# Sheet1_4651_MEZ.net
KiCad netlist of a schematic drawn in Altium Designer
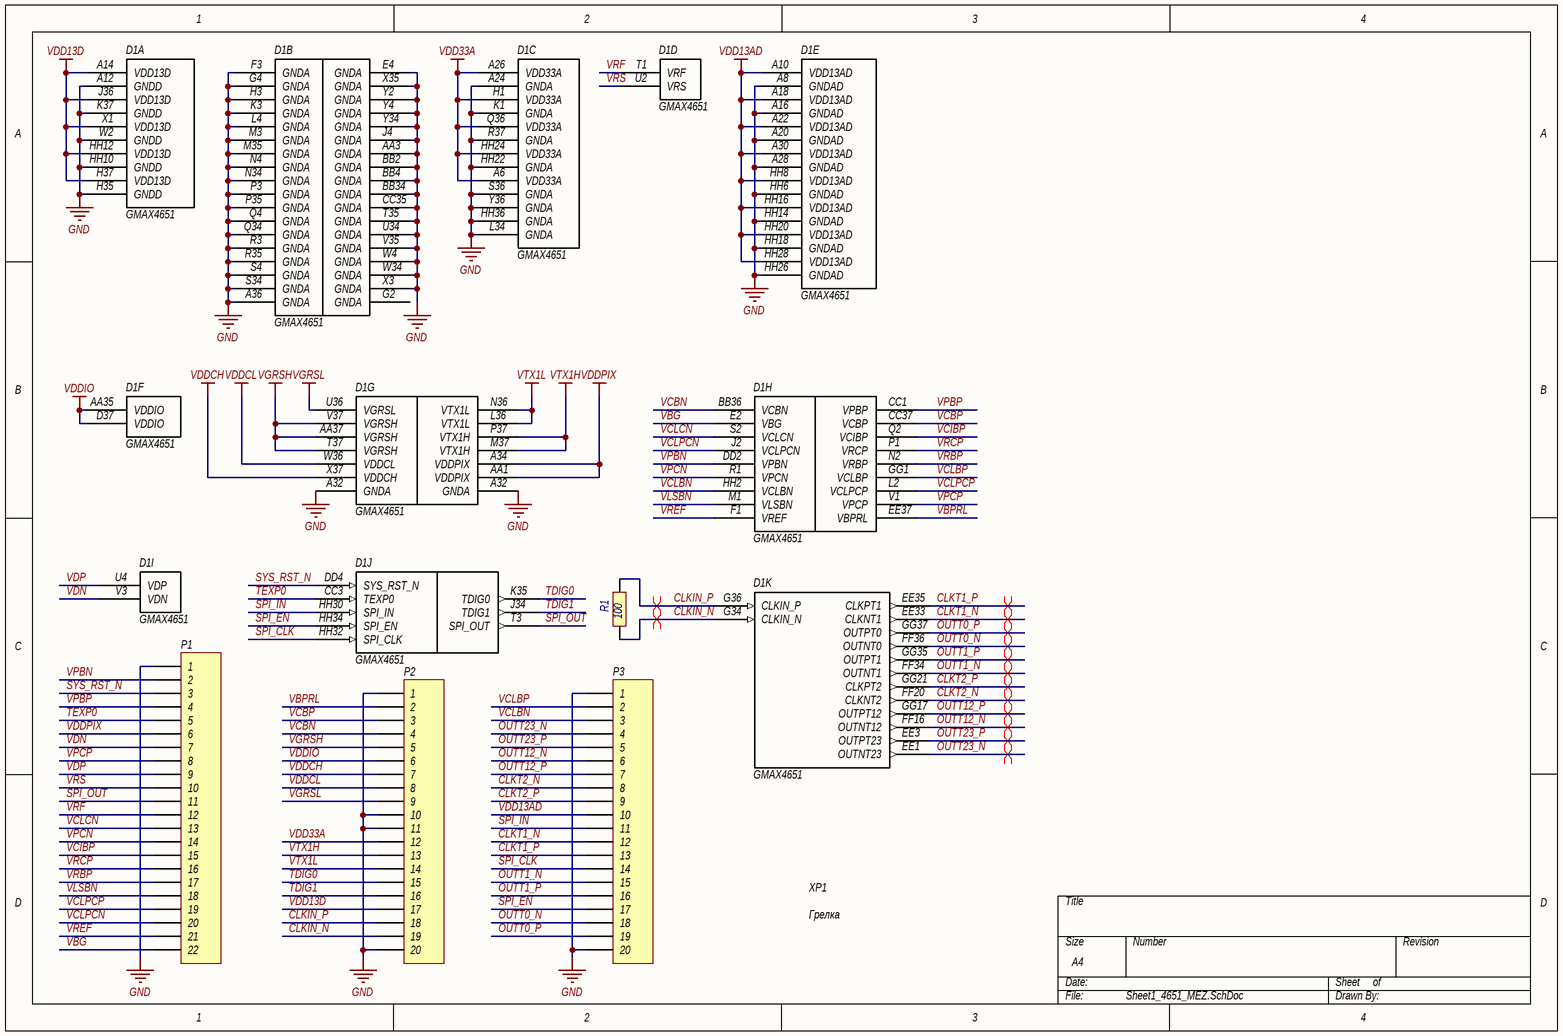
[diagram p0: Sheet1_4651_MEZ.SchDoc]

(export (version "E")
  (design (tool "Eeschema 10.0.6"))
  (components
    (comp (ref "D1") (value "GMAX4651") (footprint "GMAX4651") (libsource (lib "Schlib") (part "GMAX4651")))
    (comp (ref "P1")
      (value "Header 22")
      (footprint "HDR1X22")
      (description "Header, 22-Pin")
      (fields (field (name "PUBLISHER") "Altium Limited"))
      (libsource (lib "Miscellaneous Connectors") (part "Header 22"))
    )
    (comp (ref "P2")
      (value "Header 20")
      (footprint "HDR1X20")
      (description "Header, 20-Pin")
      (fields (field (name "PUBLISHER") "Altium Limited"))
      (libsource (lib "Miscellaneous Connectors") (part "Header 20"))
    )
    (comp (ref "P3")
      (value "Header 20")
      (footprint "HDR1X20")
      (description "Header, 20-Pin")
      (fields (field (name "PUBLISHER") "Altium Limited"))
      (libsource (lib "Miscellaneous Connectors") (part "Header 20"))
    )
    (comp (ref "R1") (value "100") (footprint "RES") (libsource (lib "Schlib") (part "RES")))
    (comp (ref "XP1") (value "Грелка") (footprint "Грелка") (libsource (lib "VPL") (part "Грелка")))
  )
  (nets
    (net (code "1") (name "/CLKIN_N") (class "Default")
      (node (ref "D1") (pin "G34") (pinfunction "CLKIN_N_G34") (pintype "input"))
      (node (ref "P2") (pin "19") (pinfunction "19_19") (pintype "passive"))
      (node (ref "R1") (pin "1") (pinfunction "1_1") (pintype "passive"))
    )
    (net (code "2") (name "/CLKIN_P") (class "Default")
      (node (ref "D1") (pin "G36") (pinfunction "CLKIN_P_G36") (pintype "input"))
      (node (ref "P2") (pin "18") (pinfunction "18_18") (pintype "passive"))
      (node (ref "R1") (pin "2") (pinfunction "2_2") (pintype "passive"))
    )
    (net (code "3") (name "/CLKT1_N") (class "Default")
      (node (ref "D1") (pin "EE33") (pinfunction "CLKNT1_EE33") (pintype "output"))
      (node (ref "P3") (pin "12") (pinfunction "12_12") (pintype "passive"))
    )
    (net (code "4") (name "/CLKT1_P") (class "Default")
      (node (ref "D1") (pin "EE35") (pinfunction "CLKPT1_EE35") (pintype "output"))
      (node (ref "P3") (pin "13") (pinfunction "13_13") (pintype "passive"))
    )
    (net (code "5") (name "/CLKT2_N") (class "Default")
      (node (ref "D1") (pin "FF20") (pinfunction "CLKNT2_FF20") (pintype "output"))
      (node (ref "P3") (pin "8") (pinfunction "8_8") (pintype "passive"))
    )
    (net (code "6") (name "/CLKT2_P") (class "Default")
      (node (ref "D1") (pin "GG21") (pinfunction "CLKPT2_GG21") (pintype "output"))
      (node (ref "P3") (pin "9") (pinfunction "9_9") (pintype "passive"))
    )
    (net (code "7") (name "/OUTT0_N") (class "Default")
      (node (ref "D1") (pin "FF36") (pinfunction "OUTNT0_FF36") (pintype "output"))
      (node (ref "P3") (pin "18") (pinfunction "18_18") (pintype "passive"))
    )
    (net (code "8") (name "/OUTT0_P") (class "Default")
      (node (ref "D1") (pin "GG37") (pinfunction "OUTPT0_GG37") (pintype "output"))
      (node (ref "P3") (pin "19") (pinfunction "19_19") (pintype "passive"))
    )
    (net (code "9") (name "/OUTT1_N") (class "Default")
      (node (ref "D1") (pin "FF34") (pinfunction "OUTNT1_FF34") (pintype "output"))
      (node (ref "P3") (pin "15") (pinfunction "15_15") (pintype "passive"))
    )
    (net (code "10") (name "/OUTT1_P") (class "Default")
      (node (ref "D1") (pin "GG35") (pinfunction "OUTPT1_GG35") (pintype "output"))
      (node (ref "P3") (pin "16") (pinfunction "16_16") (pintype "passive"))
    )
    (net (code "11") (name "/OUTT12_N") (class "Default")
      (node (ref "D1") (pin "FF16") (pinfunction "OUTNT12_FF16") (pintype "output"))
      (node (ref "P3") (pin "6") (pinfunction "6_6") (pintype "passive"))
    )
    (net (code "12") (name "/OUTT12_P") (class "Default")
      (node (ref "D1") (pin "GG17") (pinfunction "OUTPT12_GG17") (pintype "output"))
      (node (ref "P3") (pin "7") (pinfunction "7_7") (pintype "passive"))
    )
    (net (code "13") (name "/OUTT23_N") (class "Default")
      (node (ref "D1") (pin "EE1") (pinfunction "OUTNT23_EE1") (pintype "output"))
      (node (ref "P3") (pin "4") (pinfunction "4_4") (pintype "passive"))
    )
    (net (code "14") (name "/OUTT23_P") (class "Default")
      (node (ref "D1") (pin "EE3") (pinfunction "OUTPT23_EE3") (pintype "output"))
      (node (ref "P3") (pin "5") (pinfunction "5_5") (pintype "passive"))
    )
    (net (code "15") (name "/SPI_CLK") (class "Default")
      (node (ref "D1") (pin "HH32") (pinfunction "SPI_CLK_HH32") (pintype "input"))
      (node (ref "P3") (pin "14") (pinfunction "14_14") (pintype "passive"))
    )
    (net (code "16") (name "/SPI_EN") (class "Default")
      (node (ref "D1") (pin "HH34") (pinfunction "SPI_EN_HH34") (pintype "input"))
      (node (ref "P3") (pin "17") (pinfunction "17_17") (pintype "passive"))
    )
    (net (code "17") (name "/SPI_IN") (class "Default")
      (node (ref "D1") (pin "HH30") (pinfunction "SPI_IN_HH30") (pintype "input"))
      (node (ref "P3") (pin "11") (pinfunction "11_11") (pintype "passive"))
    )
    (net (code "18") (name "/SPI_OUT") (class "Default")
      (node (ref "D1") (pin "T3") (pinfunction "SPI_OUT_T3") (pintype "output"))
      (node (ref "P1") (pin "11") (pinfunction "11_11") (pintype "passive"))
    )
    (net (code "19") (name "/SYS_RST_N") (class "Default")
      (node (ref "D1") (pin "DD4") (pinfunction "SYS_RST_N_DD4") (pintype "input"))
      (node (ref "P1") (pin "3") (pinfunction "3_3") (pintype "passive"))
    )
    (net (code "20") (name "/TDIG0") (class "Default")
      (node (ref "D1") (pin "K35") (pinfunction "TDIG0_K35") (pintype "output"))
      (node (ref "P2") (pin "15") (pinfunction "15_15") (pintype "passive"))
    )
    (net (code "21") (name "/TDIG1") (class "Default")
      (node (ref "D1") (pin "J34") (pinfunction "TDIG1_J34") (pintype "output"))
      (node (ref "P2") (pin "16") (pinfunction "16_16") (pintype "passive"))
    )
    (net (code "22") (name "/TEXP0") (class "Default")
      (node (ref "D1") (pin "CC3") (pinfunction "TEXP0_CC3") (pintype "input"))
      (node (ref "P1") (pin "5") (pinfunction "5_5") (pintype "passive"))
    )
    (net (code "23") (name "/VBG") (class "Default")
      (node (ref "D1") (pin "E2") (pinfunction "VBG_E2") (pintype "passive"))
      (node (ref "P1") (pin "22") (pinfunction "22_22") (pintype "passive"))
    )
    (net (code "24") (name "/VBPRL") (class "Default")
      (node (ref "D1") (pin "EE37") (pinfunction "VBPRL_EE37") (pintype "passive"))
      (node (ref "P2") (pin "2") (pinfunction "2_2") (pintype "passive"))
    )
    (net (code "25") (name "/VCBN") (class "Default")
      (node (ref "D1") (pin "BB36") (pinfunction "VCBN_BB36") (pintype "passive"))
      (node (ref "P2") (pin "4") (pinfunction "4_4") (pintype "passive"))
    )
    (net (code "26") (name "/VCBP") (class "Default")
      (node (ref "D1") (pin "CC37") (pinfunction "VCBP_CC37") (pintype "passive"))
      (node (ref "P2") (pin "3") (pinfunction "3_3") (pintype "passive"))
    )
    (net (code "27") (name "/VCIBP") (class "Default")
      (node (ref "D1") (pin "Q2") (pinfunction "VCIBP_Q2") (pintype "passive"))
      (node (ref "P1") (pin "15") (pinfunction "15_15") (pintype "passive"))
    )
    (net (code "28") (name "/VCLBN") (class "Default")
      (node (ref "D1") (pin "HH2") (pinfunction "VCLBN_HH2") (pintype "passive"))
      (node (ref "P3") (pin "3") (pinfunction "3_3") (pintype "passive"))
    )
    (net (code "29") (name "/VCLBP") (class "Default")
      (node (ref "D1") (pin "GG1") (pinfunction "VCLBP_GG1") (pintype "passive"))
      (node (ref "P3") (pin "2") (pinfunction "2_2") (pintype "passive"))
    )
    (net (code "30") (name "/VCLCN") (class "Default")
      (node (ref "D1") (pin "S2") (pinfunction "VCLCN_S2") (pintype "passive"))
      (node (ref "P1") (pin "13") (pinfunction "13_13") (pintype "passive"))
    )
    (net (code "31") (name "/VCLPCN") (class "Default")
      (node (ref "D1") (pin "J2") (pinfunction "VCLPCN_J2") (pintype "passive"))
      (node (ref "P1") (pin "20") (pinfunction "20_20") (pintype "passive"))
    )
    (net (code "32") (name "/VCLPCP") (class "Default")
      (node (ref "D1") (pin "L2") (pinfunction "VCLPCP_L2") (pintype "passive"))
      (node (ref "P1") (pin "19") (pinfunction "19_19") (pintype "passive"))
    )
    (net (code "33") (name "/VDN") (class "Default")
      (node (ref "D1") (pin "V3") (pinfunction "VDN_V3") (pintype "passive"))
      (node (ref "P1") (pin "7") (pinfunction "7_7") (pintype "passive"))
    )
    (net (code "34") (name "/VDP") (class "Default")
      (node (ref "D1") (pin "U4") (pinfunction "VDP_U4") (pintype "passive"))
      (node (ref "P1") (pin "9") (pinfunction "9_9") (pintype "passive"))
    )
    (net (code "35") (name "/VLSBN") (class "Default")
      (node (ref "D1") (pin "M1") (pinfunction "VLSBN_M1") (pintype "passive"))
      (node (ref "P1") (pin "18") (pinfunction "18_18") (pintype "passive"))
    )
    (net (code "36") (name "/VPBN") (class "Default")
      (node (ref "D1") (pin "DD2") (pinfunction "VPBN_DD2") (pintype "passive"))
      (node (ref "P1") (pin "2") (pinfunction "2_2") (pintype "passive"))
    )
    (net (code "37") (name "/VPBP") (class "Default")
      (node (ref "D1") (pin "CC1") (pinfunction "VPBP_CC1") (pintype "passive"))
      (node (ref "P1") (pin "4") (pinfunction "4_4") (pintype "passive"))
    )
    (net (code "38") (name "/VPCN") (class "Default")
      (node (ref "D1") (pin "R1") (pinfunction "VPCN_R1") (pintype "passive"))
      (node (ref "P1") (pin "14") (pinfunction "14_14") (pintype "passive"))
    )
    (net (code "39") (name "/VPCP") (class "Default")
      (node (ref "D1") (pin "V1") (pinfunction "VPCP_V1") (pintype "passive"))
      (node (ref "P1") (pin "8") (pinfunction "8_8") (pintype "passive"))
    )
    (net (code "40") (name "/VRBP") (class "Default")
      (node (ref "D1") (pin "N2") (pinfunction "VRBP_N2") (pintype "passive"))
      (node (ref "P1") (pin "17") (pinfunction "17_17") (pintype "passive"))
    )
    (net (code "41") (name "/VRCP") (class "Default")
      (node (ref "D1") (pin "P1") (pinfunction "VRCP_P1") (pintype "passive"))
      (node (ref "P1") (pin "16") (pinfunction "16_16") (pintype "passive"))
    )
    (net (code "42") (name "/VREF") (class "Default")
      (node (ref "D1") (pin "F1") (pinfunction "VREF_F1") (pintype "passive"))
      (node (ref "P1") (pin "21") (pinfunction "21_21") (pintype "passive"))
    )
    (net (code "43") (name "/VRF") (class "Default")
      (node (ref "D1") (pin "T1") (pinfunction "VRF_T1") (pintype "passive"))
      (node (ref "P1") (pin "12") (pinfunction "12_12") (pintype "passive"))
    )
    (net (code "44") (name "/VRS") (class "Default")
      (node (ref "D1") (pin "U2") (pinfunction "VRS_U2") (pintype "passive"))
      (node (ref "P1") (pin "10") (pinfunction "10_10") (pintype "passive"))
    )
    (net (code "45") (name "GND") (class "Default")
      (node (ref "D1") (pin "A12") (pinfunction "GNDD_A12") (pintype "passive"))
      (node (ref "D1") (pin "A16") (pinfunction "GNDAD_A16") (pintype "passive"))
      (node (ref "D1") (pin "A20") (pinfunction "GNDAD_A20") (pintype "passive"))
      (node (ref "D1") (pin "A24") (pinfunction "GNDA_A24") (pintype "passive"))
      (node (ref "D1") (pin "A28") (pinfunction "GNDAD_A28") (pintype "passive"))
      (node (ref "D1") (pin "A32") (pinfunction "GNDA_A32") (pintype "passive"))
      (node (ref "D1") (pin "A36") (pinfunction "GNDA_A36") (pintype "passive"))
      (node (ref "D1") (pin "A8") (pinfunction "GNDAD_A8") (pintype "passive"))
      (node (ref "D1") (pin "AA3") (pinfunction "GNDA_AA3") (pintype "passive"))
      (node (ref "D1") (pin "BB2") (pinfunction "GNDA_BB2") (pintype "passive"))
      (node (ref "D1") (pin "BB34") (pinfunction "GNDA_BB34") (pintype "passive"))
      (node (ref "D1") (pin "BB4") (pinfunction "GNDA_BB4") (pintype "passive"))
      (node (ref "D1") (pin "CC35") (pinfunction "GNDA_CC35") (pintype "passive"))
      (node (ref "D1") (pin "E4") (pinfunction "GNDA_E4") (pintype "passive"))
      (node (ref "D1") (pin "F3") (pinfunction "GNDA_F3") (pintype "passive"))
      (node (ref "D1") (pin "G4") (pinfunction "GNDA_G4") (pintype "passive"))
      (node (ref "D1") (pin "H3") (pinfunction "GNDA_H3") (pintype "passive"))
      (node (ref "D1") (pin "H35") (pinfunction "GNDD_H35") (pintype "passive"))
      (node (ref "D1") (pin "HH10") (pinfunction "GNDD_HH10") (pintype "passive"))
      (node (ref "D1") (pin "HH14") (pinfunction "GNDAD_HH14") (pintype "passive"))
      (node (ref "D1") (pin "HH18") (pinfunction "GNDAD_HH18") (pintype "passive"))
      (node (ref "D1") (pin "HH22") (pinfunction "GNDA_HH22") (pintype "passive"))
      (node (ref "D1") (pin "HH26") (pinfunction "GNDAD_HH26") (pintype "passive"))
      (node (ref "D1") (pin "HH36") (pinfunction "GNDA_HH36") (pintype "passive"))
      (node (ref "D1") (pin "HH6") (pinfunction "GNDAD_HH6") (pintype "passive"))
      (node (ref "D1") (pin "J4") (pinfunction "GNDA_J4") (pintype "passive"))
      (node (ref "D1") (pin "K1") (pinfunction "GNDA_K1") (pintype "passive"))
      (node (ref "D1") (pin "K3") (pinfunction "GNDA_K3") (pintype "passive"))
      (node (ref "D1") (pin "K37") (pinfunction "GNDD_K37") (pintype "passive"))
      (node (ref "D1") (pin "L34") (pinfunction "GNDA_L34") (pintype "passive"))
      (node (ref "D1") (pin "L4") (pinfunction "GNDA_L4") (pintype "passive"))
      (node (ref "D1") (pin "M3") (pinfunction "GNDA_M3") (pintype "passive"))
      (node (ref "D1") (pin "M35") (pinfunction "GNDA_M35") (pintype "passive"))
      (node (ref "D1") (pin "N34") (pinfunction "GNDA_N34") (pintype "passive"))
      (node (ref "D1") (pin "N4") (pinfunction "GNDA_N4") (pintype "passive"))
      (node (ref "D1") (pin "P3") (pinfunction "GNDA_P3") (pintype "passive"))
      (node (ref "D1") (pin "P35") (pinfunction "GNDA_P35") (pintype "passive"))
      (node (ref "D1") (pin "Q34") (pinfunction "GNDA_Q34") (pintype "passive"))
      (node (ref "D1") (pin "Q4") (pinfunction "GNDA_Q4") (pintype "passive"))
      (node (ref "D1") (pin "R3") (pinfunction "GNDA_R3") (pintype "passive"))
      (node (ref "D1") (pin "R35") (pinfunction "GNDA_R35") (pintype "passive"))
      (node (ref "D1") (pin "R37") (pinfunction "GNDA_R37") (pintype "passive"))
      (node (ref "D1") (pin "S34") (pinfunction "GNDA_S34") (pintype "passive"))
      (node (ref "D1") (pin "S36") (pinfunction "GNDA_S36") (pintype "passive"))
      (node (ref "D1") (pin "S4") (pinfunction "GNDA_S4") (pintype "passive"))
      (node (ref "D1") (pin "T35") (pinfunction "GNDA_T35") (pintype "passive"))
      (node (ref "D1") (pin "U34") (pinfunction "GNDA_U34") (pintype "passive"))
      (node (ref "D1") (pin "V35") (pinfunction "GNDA_V35") (pintype "passive"))
      (node (ref "D1") (pin "W2") (pinfunction "GNDD_W2") (pintype "passive"))
      (node (ref "D1") (pin "W34") (pinfunction "GNDA_W34") (pintype "passive"))
      (node (ref "D1") (pin "W4") (pinfunction "GNDA_W4") (pintype "passive"))
      (node (ref "D1") (pin "X3") (pinfunction "GNDA_X3") (pintype "passive"))
      (node (ref "D1") (pin "X35") (pinfunction "GNDA_X35") (pintype "passive"))
      (node (ref "D1") (pin "Y2") (pinfunction "GNDA_Y2") (pintype "passive"))
      (node (ref "D1") (pin "Y34") (pinfunction "GNDA_Y34") (pintype "passive"))
      (node (ref "D1") (pin "Y36") (pinfunction "GNDA_Y36") (pintype "passive"))
      (node (ref "D1") (pin "Y4") (pinfunction "GNDA_Y4") (pintype "passive"))
      (node (ref "P1") (pin "1") (pinfunction "1_1") (pintype "passive"))
      (node (ref "P2") (pin "1") (pinfunction "1_1") (pintype "passive"))
      (node (ref "P2") (pin "10") (pinfunction "10_10") (pintype "passive"))
      (node (ref "P2") (pin "11") (pinfunction "11_11") (pintype "passive"))
      (node (ref "P2") (pin "20") (pinfunction "20_20") (pintype "passive"))
      (node (ref "P3") (pin "1") (pinfunction "1_1") (pintype "passive"))
      (node (ref "P3") (pin "20") (pinfunction "20_20") (pintype "passive"))
    )
    (net (code "46") (name "VDD13AD") (class "Default")
      (node (ref "D1") (pin "A10") (pinfunction "VDD13AD_A10") (pintype "passive"))
      (node (ref "D1") (pin "A18") (pinfunction "VDD13AD_A18") (pintype "passive"))
      (node (ref "D1") (pin "A22") (pinfunction "VDD13AD_A22") (pintype "passive"))
      (node (ref "D1") (pin "A30") (pinfunction "VDD13AD_A30") (pintype "passive"))
      (node (ref "D1") (pin "HH16") (pinfunction "VDD13AD_HH16") (pintype "passive"))
      (node (ref "D1") (pin "HH20") (pinfunction "VDD13AD_HH20") (pintype "passive"))
      (node (ref "D1") (pin "HH28") (pinfunction "VDD13AD_HH28") (pintype "passive"))
      (node (ref "D1") (pin "HH8") (pinfunction "VDD13AD_HH8") (pintype "passive"))
      (node (ref "P3") (pin "10") (pinfunction "10_10") (pintype "passive"))
    )
    (net (code "47") (name "VDD13D") (class "Default")
      (node (ref "D1") (pin "A14") (pinfunction "VDD13D_A14") (pintype "passive"))
      (node (ref "D1") (pin "H37") (pinfunction "VDD13D_H37") (pintype "passive"))
      (node (ref "D1") (pin "HH12") (pinfunction "VDD13D_HH12") (pintype "passive"))
      (node (ref "D1") (pin "J36") (pinfunction "VDD13D_J36") (pintype "passive"))
      (node (ref "D1") (pin "X1") (pinfunction "VDD13D_X1") (pintype "passive"))
      (node (ref "P2") (pin "17") (pinfunction "17_17") (pintype "passive"))
    )
    (net (code "48") (name "VDD33A") (class "Default")
      (node (ref "D1") (pin "A26") (pinfunction "VDD33A_A26") (pintype "passive"))
      (node (ref "D1") (pin "A6") (pinfunction "VDD33A_A6") (pintype "passive"))
      (node (ref "D1") (pin "H1") (pinfunction "VDD33A_H1") (pintype "passive"))
      (node (ref "D1") (pin "HH24") (pinfunction "VDD33A_HH24") (pintype "passive"))
      (node (ref "D1") (pin "Q36") (pinfunction "VDD33A_Q36") (pintype "passive"))
      (node (ref "P2") (pin "12") (pinfunction "12_12") (pintype "passive"))
    )
    (net (code "49") (name "VDDCH") (class "Default")
      (node (ref "D1") (pin "X37") (pinfunction "VDDCH_X37") (pintype "passive"))
      (node (ref "P2") (pin "7") (pinfunction "7_7") (pintype "passive"))
    )
    (net (code "50") (name "VDDCL") (class "Default")
      (node (ref "D1") (pin "W36") (pinfunction "VDDCL_W36") (pintype "passive"))
      (node (ref "P2") (pin "8") (pinfunction "8_8") (pintype "passive"))
    )
    (net (code "51") (name "VDDIO") (class "Default")
      (node (ref "D1") (pin "AA35") (pinfunction "VDDIO_AA35") (pintype "passive"))
      (node (ref "D1") (pin "D37") (pinfunction "VDDIO_D37") (pintype "passive"))
      (node (ref "P2") (pin "6") (pinfunction "6_6") (pintype "passive"))
    )
    (net (code "52") (name "VDDPIX") (class "Default")
      (node (ref "D1") (pin "A34") (pinfunction "VDDPIX_A34") (pintype "passive"))
      (node (ref "D1") (pin "AA1") (pinfunction "VDDPIX_AA1") (pintype "passive"))
      (node (ref "P1") (pin "6") (pinfunction "6_6") (pintype "passive"))
    )
    (net (code "53") (name "VGRSH") (class "Default")
      (node (ref "D1") (pin "AA37") (pinfunction "VGRSH_AA37") (pintype "passive"))
      (node (ref "D1") (pin "T37") (pinfunction "VGRSH_T37") (pintype "passive"))
      (node (ref "D1") (pin "V37") (pinfunction "VGRSH_V37") (pintype "passive"))
      (node (ref "P2") (pin "5") (pinfunction "5_5") (pintype "passive"))
    )
    (net (code "54") (name "VGRSL") (class "Default")
      (node (ref "D1") (pin "U36") (pinfunction "VGRSL_U36") (pintype "passive"))
      (node (ref "P2") (pin "9") (pinfunction "9_9") (pintype "passive"))
    )
    (net (code "55") (name "VTX1H") (class "Default")
      (node (ref "D1") (pin "M37") (pinfunction "VTX1H_M37") (pintype "passive"))
      (node (ref "D1") (pin "P37") (pinfunction "VTX1H_P37") (pintype "passive"))
      (node (ref "P2") (pin "13") (pinfunction "13_13") (pintype "passive"))
    )
    (net (code "56") (name "VTX1L") (class "Default")
      (node (ref "D1") (pin "L36") (pinfunction "VTX1L_L36") (pintype "passive"))
      (node (ref "D1") (pin "N36") (pinfunction "VTX1L_N36") (pintype "passive"))
      (node (ref "P2") (pin "14") (pinfunction "14_14") (pintype "passive"))
    )
    (net (code "57") (name "unconnected-(D1B-GNDA-PadG2)") (class "Default")
      (node (ref "D1") (pin "G2") (pinfunction "GNDA_G2") (pintype "passive"))
    )
  )
)
